# firely.net
KiCad netlist of a schematic drawn in EAGLE
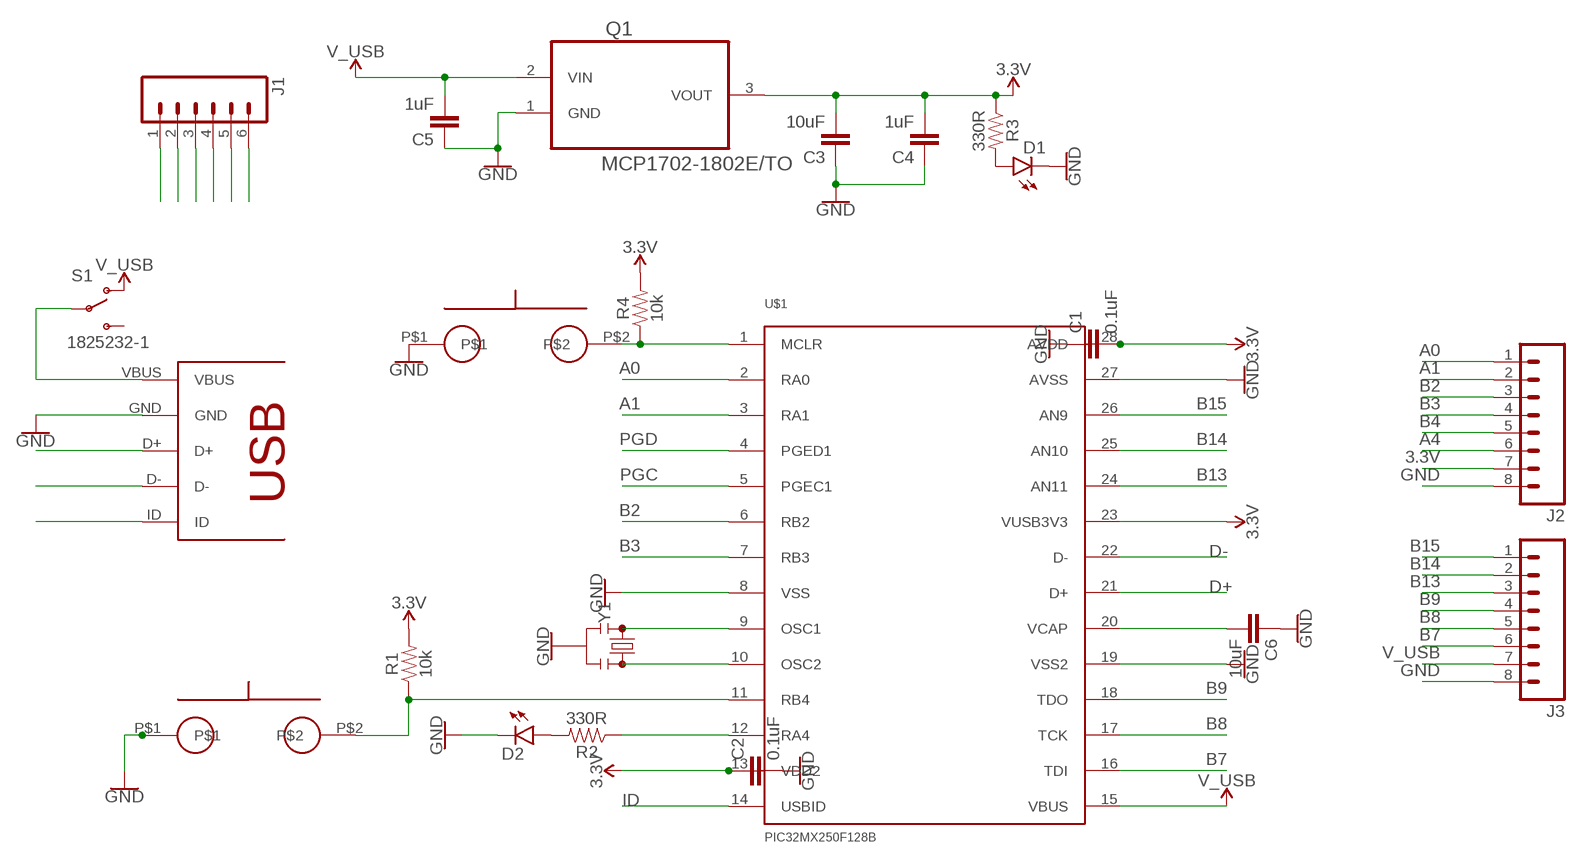
[diagram p0: schematic, sheet 1]

(export (version "E")
  (design (tool "Eeschema 10.0.6"))
  (components
    (comp (ref "C1")
      (value "0.1uF")
      (footprint "eagle-import:PTH_VERT_CAP")
      (libsource (lib "eagle-import") (part "CAPVERT_CAP"))
    )
    (comp (ref "C2")
      (value "0.1uF")
      (footprint "eagle-import:PTH_VERT_CAP")
      (libsource (lib "eagle-import") (part "CAPVERT_CAP"))
    )
    (comp (ref "C3")
      (value "10uF")
      (footprint "eagle-import:PTH_VERT_CAP")
      (libsource (lib "eagle-import") (part "CAPVERT_CAP"))
    )
    (comp (ref "C4")
      (value "1uF")
      (footprint "eagle-import:PTH_VERT_CAP")
      (libsource (lib "eagle-import") (part "CAPVERT_CAP"))
    )
    (comp (ref "C5")
      (value "1uF")
      (footprint "eagle-import:PTH_VERT_CAP")
      (libsource (lib "eagle-import") (part "CAPVERT_CAP"))
    )
    (comp (ref "C6")
      (value "10uF")
      (footprint "eagle-import:PTH_VERT_CAP")
      (libsource (lib "eagle-import") (part "CAPVERT_CAP"))
    )
    (comp (ref "D1")
      (value "LED3MM")
      (footprint "eagle-import:LED3MM")
      (libsource (lib "eagle-import") (part "LED3MM"))
    )
    (comp (ref "D2")
      (value "LED3MM")
      (footprint "eagle-import:LED3MM")
      (libsource (lib "eagle-import") (part "LED3MM"))
    )
    (comp (ref "J1")
      (value "M06SILK_FEMALE_PTH")
      (footprint "eagle-import:1X06")
      (libsource (lib "eagle-import") (part "M06SILK_FEMALE_PTH"))
    )
    (comp (ref "J2")
      (value "M08")
      (footprint "eagle-import:1X08_ROUND")
      (libsource (lib "eagle-import") (part "M08"))
    )
    (comp (ref "J3")
      (value "M08")
      (footprint "eagle-import:1X08_ROUND")
      (libsource (lib "eagle-import") (part "M08"))
    )
    (comp (ref "Q1")
      (value "MCP1702-1802E/TO")
      (footprint "eagle-import:TO127P254X533-3")
      (libsource (lib "eagle-import") (part "MCP1702-1802E/TO"))
    )
    (comp (ref "R1")
      (value "10k")
      (footprint "eagle-import:AXIAL-0.3")
      (libsource (lib "eagle-import") (part "1KOHM-HORIZ-1/4W-5%"))
    )
    (comp (ref "R2")
      (value "330R")
      (footprint "eagle-import:AXIAL-0.3")
      (libsource (lib "eagle-import") (part "1KOHM-HORIZ-1/4W-5%"))
    )
    (comp (ref "R3")
      (value "330R")
      (footprint "eagle-import:AXIAL-0.3")
      (libsource (lib "eagle-import") (part "1KOHM-HORIZ-1/4W-5%"))
    )
    (comp (ref "R4")
      (value "10k")
      (footprint "eagle-import:AXIAL-0.3")
      (libsource (lib "eagle-import") (part "1KOHM-HORIZ-1/4W-5%"))
    )
    (comp (ref "S1")
      (value "1825232-1")
      (footprint "eagle-import:1825232-1")
      (libsource (lib "eagle-import") (part "1825232-1"))
    )
    (comp (ref "U$1")
      (value "PIC32MX250F128B")
      (footprint "eagle-import:DIP28")
      (libsource (lib "eagle-import") (part "PIC32MX250F128B"))
    )
    (comp (ref "U$2")
      (value "EVQ11")
      (footprint "eagle-import:EVQ11")
      (libsource (lib "eagle-import") (part "EVQ11"))
    )
    (comp (ref "U$3")
      (value "USB_FULL")
      (footprint "eagle-import:USB-MB-H")
      (libsource (lib "eagle-import") (part "USB_FULL"))
    )
    (comp (ref "U$4")
      (value "EVQ11")
      (footprint "eagle-import:EVQ11")
      (libsource (lib "eagle-import") (part "EVQ11"))
    )
    (comp (ref "Y1")
      (value "RESONATORPTH-7.6X3.8")
      (footprint "eagle-import:RESONATOR-PTH-7.6X3.8")
      (libsource (lib "eagle-import") (part "RESONATORPTH-7.6X3.8"))
    )
  )
  (nets
    (net (code "1") (name "/A0") (class "Default")
      (node (ref "J2") (pin "1") (pinfunction "1_1") (pintype "passive"))
      (node (ref "U$1") (pin "2") (pinfunction "RA0_2") (pintype "bidirectional"))
    )
    (net (code "2") (name "/A1") (class "Default")
      (node (ref "J2") (pin "2") (pinfunction "2_2") (pintype "passive"))
      (node (ref "U$1") (pin "3") (pinfunction "RA1_3") (pintype "bidirectional"))
    )
    (net (code "3") (name "/A4") (class "Default")
      (node (ref "J2") (pin "6") (pinfunction "6_6") (pintype "passive"))
      (node (ref "R2") (pin "P$1") (pinfunction "1_P$1") (pintype "passive"))
      (node (ref "U$1") (pin "12") (pinfunction "RA4_12") (pintype "bidirectional"))
    )
    (net (code "4") (name "/B2") (class "Default")
      (node (ref "J2") (pin "3") (pinfunction "3_3") (pintype "passive"))
      (node (ref "U$1") (pin "6") (pinfunction "RB2_6") (pintype "bidirectional"))
    )
    (net (code "5") (name "/B3") (class "Default")
      (node (ref "J2") (pin "4") (pinfunction "4_4") (pintype "passive"))
      (node (ref "U$1") (pin "7") (pinfunction "RB3_7") (pintype "bidirectional"))
    )
    (net (code "6") (name "/B4") (class "Default")
      (node (ref "J2") (pin "5") (pinfunction "5_5") (pintype "passive"))
      (node (ref "R1") (pin "P$1") (pinfunction "1_P$1") (pintype "passive"))
      (node (ref "U$1") (pin "11") (pinfunction "RB4_11") (pintype "bidirectional"))
      (node (ref "U$2") (pin "P$2") (pinfunction "P$2_P$2") (pintype "bidirectional"))
    )
    (net (code "7") (name "/B7") (class "Default")
      (node (ref "J3") (pin "6") (pinfunction "6_6") (pintype "passive"))
      (node (ref "U$1") (pin "16") (pinfunction "TDI_16") (pintype "bidirectional"))
    )
    (net (code "8") (name "/B8") (class "Default")
      (node (ref "J3") (pin "5") (pinfunction "5_5") (pintype "passive"))
      (node (ref "U$1") (pin "17") (pinfunction "TCK_17") (pintype "bidirectional"))
    )
    (net (code "9") (name "/B9") (class "Default")
      (node (ref "J3") (pin "4") (pinfunction "4_4") (pintype "passive"))
      (node (ref "U$1") (pin "18") (pinfunction "TDO_18") (pintype "bidirectional"))
    )
    (net (code "10") (name "/B13") (class "Default")
      (node (ref "J3") (pin "3") (pinfunction "3_3") (pintype "passive"))
      (node (ref "U$1") (pin "24") (pinfunction "AN11_24") (pintype "bidirectional"))
    )
    (net (code "11") (name "/B14") (class "Default")
      (node (ref "J3") (pin "2") (pinfunction "2_2") (pintype "passive"))
      (node (ref "U$1") (pin "25") (pinfunction "AN10_25") (pintype "bidirectional"))
    )
    (net (code "12") (name "/B15") (class "Default")
      (node (ref "J3") (pin "1") (pinfunction "1_1") (pintype "passive"))
      (node (ref "U$1") (pin "26") (pinfunction "AN9_26") (pintype "bidirectional"))
    )
    (net (code "13") (name "/D+") (class "Default")
      (node (ref "U$1") (pin "21") (pinfunction "D+_21") (pintype "bidirectional"))
      (node (ref "U$3") (pin "D+") (pinfunction "D+_D+") (pintype "bidirectional"))
    )
    (net (code "14") (name "/D-") (class "Default")
      (node (ref "U$1") (pin "22") (pinfunction "D-_22") (pintype "bidirectional"))
      (node (ref "U$3") (pin "D-") (pinfunction "D-_D-") (pintype "bidirectional"))
    )
    (net (code "15") (name "/ID") (class "Default")
      (node (ref "U$1") (pin "14") (pinfunction "USBID_14") (pintype "bidirectional"))
      (node (ref "U$3") (pin "ID") (pinfunction "ID_ID") (pintype "bidirectional"))
    )
    (net (code "16") (name "/MCLR") (class "Default")
      (node (ref "J1") (pin "1") (pinfunction "1_1") (pintype "passive"))
      (node (ref "R4") (pin "P$1") (pinfunction "1_P$1") (pintype "passive"))
      (node (ref "U$1") (pin "1") (pinfunction "MCLR_1") (pintype "bidirectional"))
      (node (ref "U$4") (pin "P$2") (pinfunction "P$2_P$2") (pintype "bidirectional"))
    )
    (net (code "17") (name "/PGC") (class "Default")
      (node (ref "J1") (pin "5") (pinfunction "5_5") (pintype "passive"))
      (node (ref "U$1") (pin "5") (pinfunction "PGEC1_5") (pintype "bidirectional"))
    )
    (net (code "18") (name "/PGD") (class "Default")
      (node (ref "J1") (pin "4") (pinfunction "4_4") (pintype "passive"))
      (node (ref "U$1") (pin "4") (pinfunction "PGED1_4") (pintype "bidirectional"))
    )
    (net (code "19") (name "3.3V") (class "Default")
      (node (ref "C1") (pin "P$2") (pinfunction "2_P$2") (pintype "passive"))
      (node (ref "C2") (pin "P$1") (pinfunction "1_P$1") (pintype "passive"))
      (node (ref "C3") (pin "P$2") (pinfunction "2_P$2") (pintype "passive"))
      (node (ref "C4") (pin "P$2") (pinfunction "2_P$2") (pintype "passive"))
      (node (ref "J1") (pin "2") (pinfunction "2_2") (pintype "passive"))
      (node (ref "J2") (pin "7") (pinfunction "7_7") (pintype "passive"))
      (node (ref "Q1") (pin "3") (pinfunction "VOUT_3") (pintype "output"))
      (node (ref "R1") (pin "P$2") (pinfunction "2_P$2") (pintype "passive"))
      (node (ref "R3") (pin "P$1") (pinfunction "1_P$1") (pintype "passive"))
      (node (ref "R4") (pin "P$2") (pinfunction "2_P$2") (pintype "passive"))
      (node (ref "U$1") (pin "13") (pinfunction "VDD2_13") (pintype "bidirectional"))
      (node (ref "U$1") (pin "23") (pinfunction "VUSB3V3_23") (pintype "bidirectional"))
      (node (ref "U$1") (pin "28") (pinfunction "AVDD_28") (pintype "bidirectional"))
    )
    (net (code "20") (name "GND") (class "Default")
      (node (ref "C1") (pin "P$1") (pinfunction "1_P$1") (pintype "passive"))
      (node (ref "C2") (pin "P$2") (pinfunction "2_P$2") (pintype "passive"))
      (node (ref "C3") (pin "P$1") (pinfunction "1_P$1") (pintype "passive"))
      (node (ref "C4") (pin "P$1") (pinfunction "1_P$1") (pintype "passive"))
      (node (ref "C5") (pin "P$1") (pinfunction "1_P$1") (pintype "passive"))
      (node (ref "C6") (pin "P$1") (pinfunction "1_P$1") (pintype "passive"))
      (node (ref "D1") (pin "K") (pinfunction "C_K") (pintype "passive"))
      (node (ref "D2") (pin "K") (pinfunction "C_K") (pintype "passive"))
      (node (ref "J1") (pin "3") (pinfunction "3_3") (pintype "passive"))
      (node (ref "J2") (pin "8") (pinfunction "8_8") (pintype "passive"))
      (node (ref "J3") (pin "8") (pinfunction "8_8") (pintype "passive"))
      (node (ref "Q1") (pin "1") (pinfunction "GND_1") (pintype "passive"))
      (node (ref "U$1") (pin "19") (pinfunction "VSS2_19") (pintype "bidirectional"))
      (node (ref "U$1") (pin "27") (pinfunction "AVSS_27") (pintype "bidirectional"))
      (node (ref "U$1") (pin "8") (pinfunction "VSS_8") (pintype "bidirectional"))
      (node (ref "U$2") (pin "P$1") (pinfunction "P$1_P$1") (pintype "bidirectional"))
      (node (ref "U$3") (pin "GND") (pinfunction "GND_GND") (pintype "bidirectional"))
      (node (ref "U$4") (pin "P$1") (pinfunction "P$1_P$1") (pintype "bidirectional"))
      (node (ref "Y1") (pin "2") (pinfunction "2_2") (pintype "passive"))
    )
    (net (code "21") (name "Net-(C6-2)") (class "Default")
      (node (ref "C6") (pin "P$2") (pinfunction "2_P$2") (pintype "passive"))
      (node (ref "U$1") (pin "20") (pinfunction "VCAP_20") (pintype "bidirectional"))
    )
    (net (code "22") (name "Net-(R2-2)") (class "Default")
      (node (ref "D2") (pin "A") (pinfunction "A_A") (pintype "passive"))
      (node (ref "R2") (pin "P$2") (pinfunction "2_P$2") (pintype "passive"))
    )
    (net (code "23") (name "Net-(R3-2)") (class "Default")
      (node (ref "D1") (pin "A") (pinfunction "A_A") (pintype "passive"))
      (node (ref "R3") (pin "P$2") (pinfunction "2_P$2") (pintype "passive"))
    )
    (net (code "24") (name "Net-(S1-Pad2)") (class "Default")
      (node (ref "S1") (pin "2") (pinfunction "2_2") (pintype "passive"))
      (node (ref "U$3") (pin "VBUS") (pinfunction "VBUS_VBUS") (pintype "bidirectional"))
    )
    (net (code "25") (name "Net-(U$1-OSC1)") (class "Default")
      (node (ref "U$1") (pin "9") (pinfunction "OSC1_9") (pintype "bidirectional"))
      (node (ref "Y1") (pin "1") (pinfunction "1_1") (pintype "passive"))
    )
    (net (code "26") (name "Net-(U$1-OSC2)") (class "Default")
      (node (ref "U$1") (pin "10") (pinfunction "OSC2_10") (pintype "bidirectional"))
      (node (ref "Y1") (pin "3") (pinfunction "3_3") (pintype "passive"))
    )
    (net (code "27") (name "V_USB") (class "Default")
      (node (ref "C5") (pin "P$2") (pinfunction "2_P$2") (pintype "passive"))
      (node (ref "J3") (pin "7") (pinfunction "7_7") (pintype "passive"))
      (node (ref "Q1") (pin "2") (pinfunction "VIN_2") (pintype "input"))
      (node (ref "S1") (pin "3") (pinfunction "3_3") (pintype "passive"))
      (node (ref "U$1") (pin "15") (pinfunction "VBUS_15") (pintype "bidirectional"))
    )
    (net (code "28") (name "unconnected-(J1-Pad6)") (class "Default")
      (node (ref "J1") (pin "6") (pinfunction "6_6") (pintype "passive"))
    )
    (net (code "29") (name "unconnected-(S1-Pad1)") (class "Default")
      (node (ref "S1") (pin "1") (pinfunction "1_1") (pintype "passive"))
    )
  )
)
